# 06_SOM_Console.net
KiCad netlist of a schematic drawn in Altium Designer
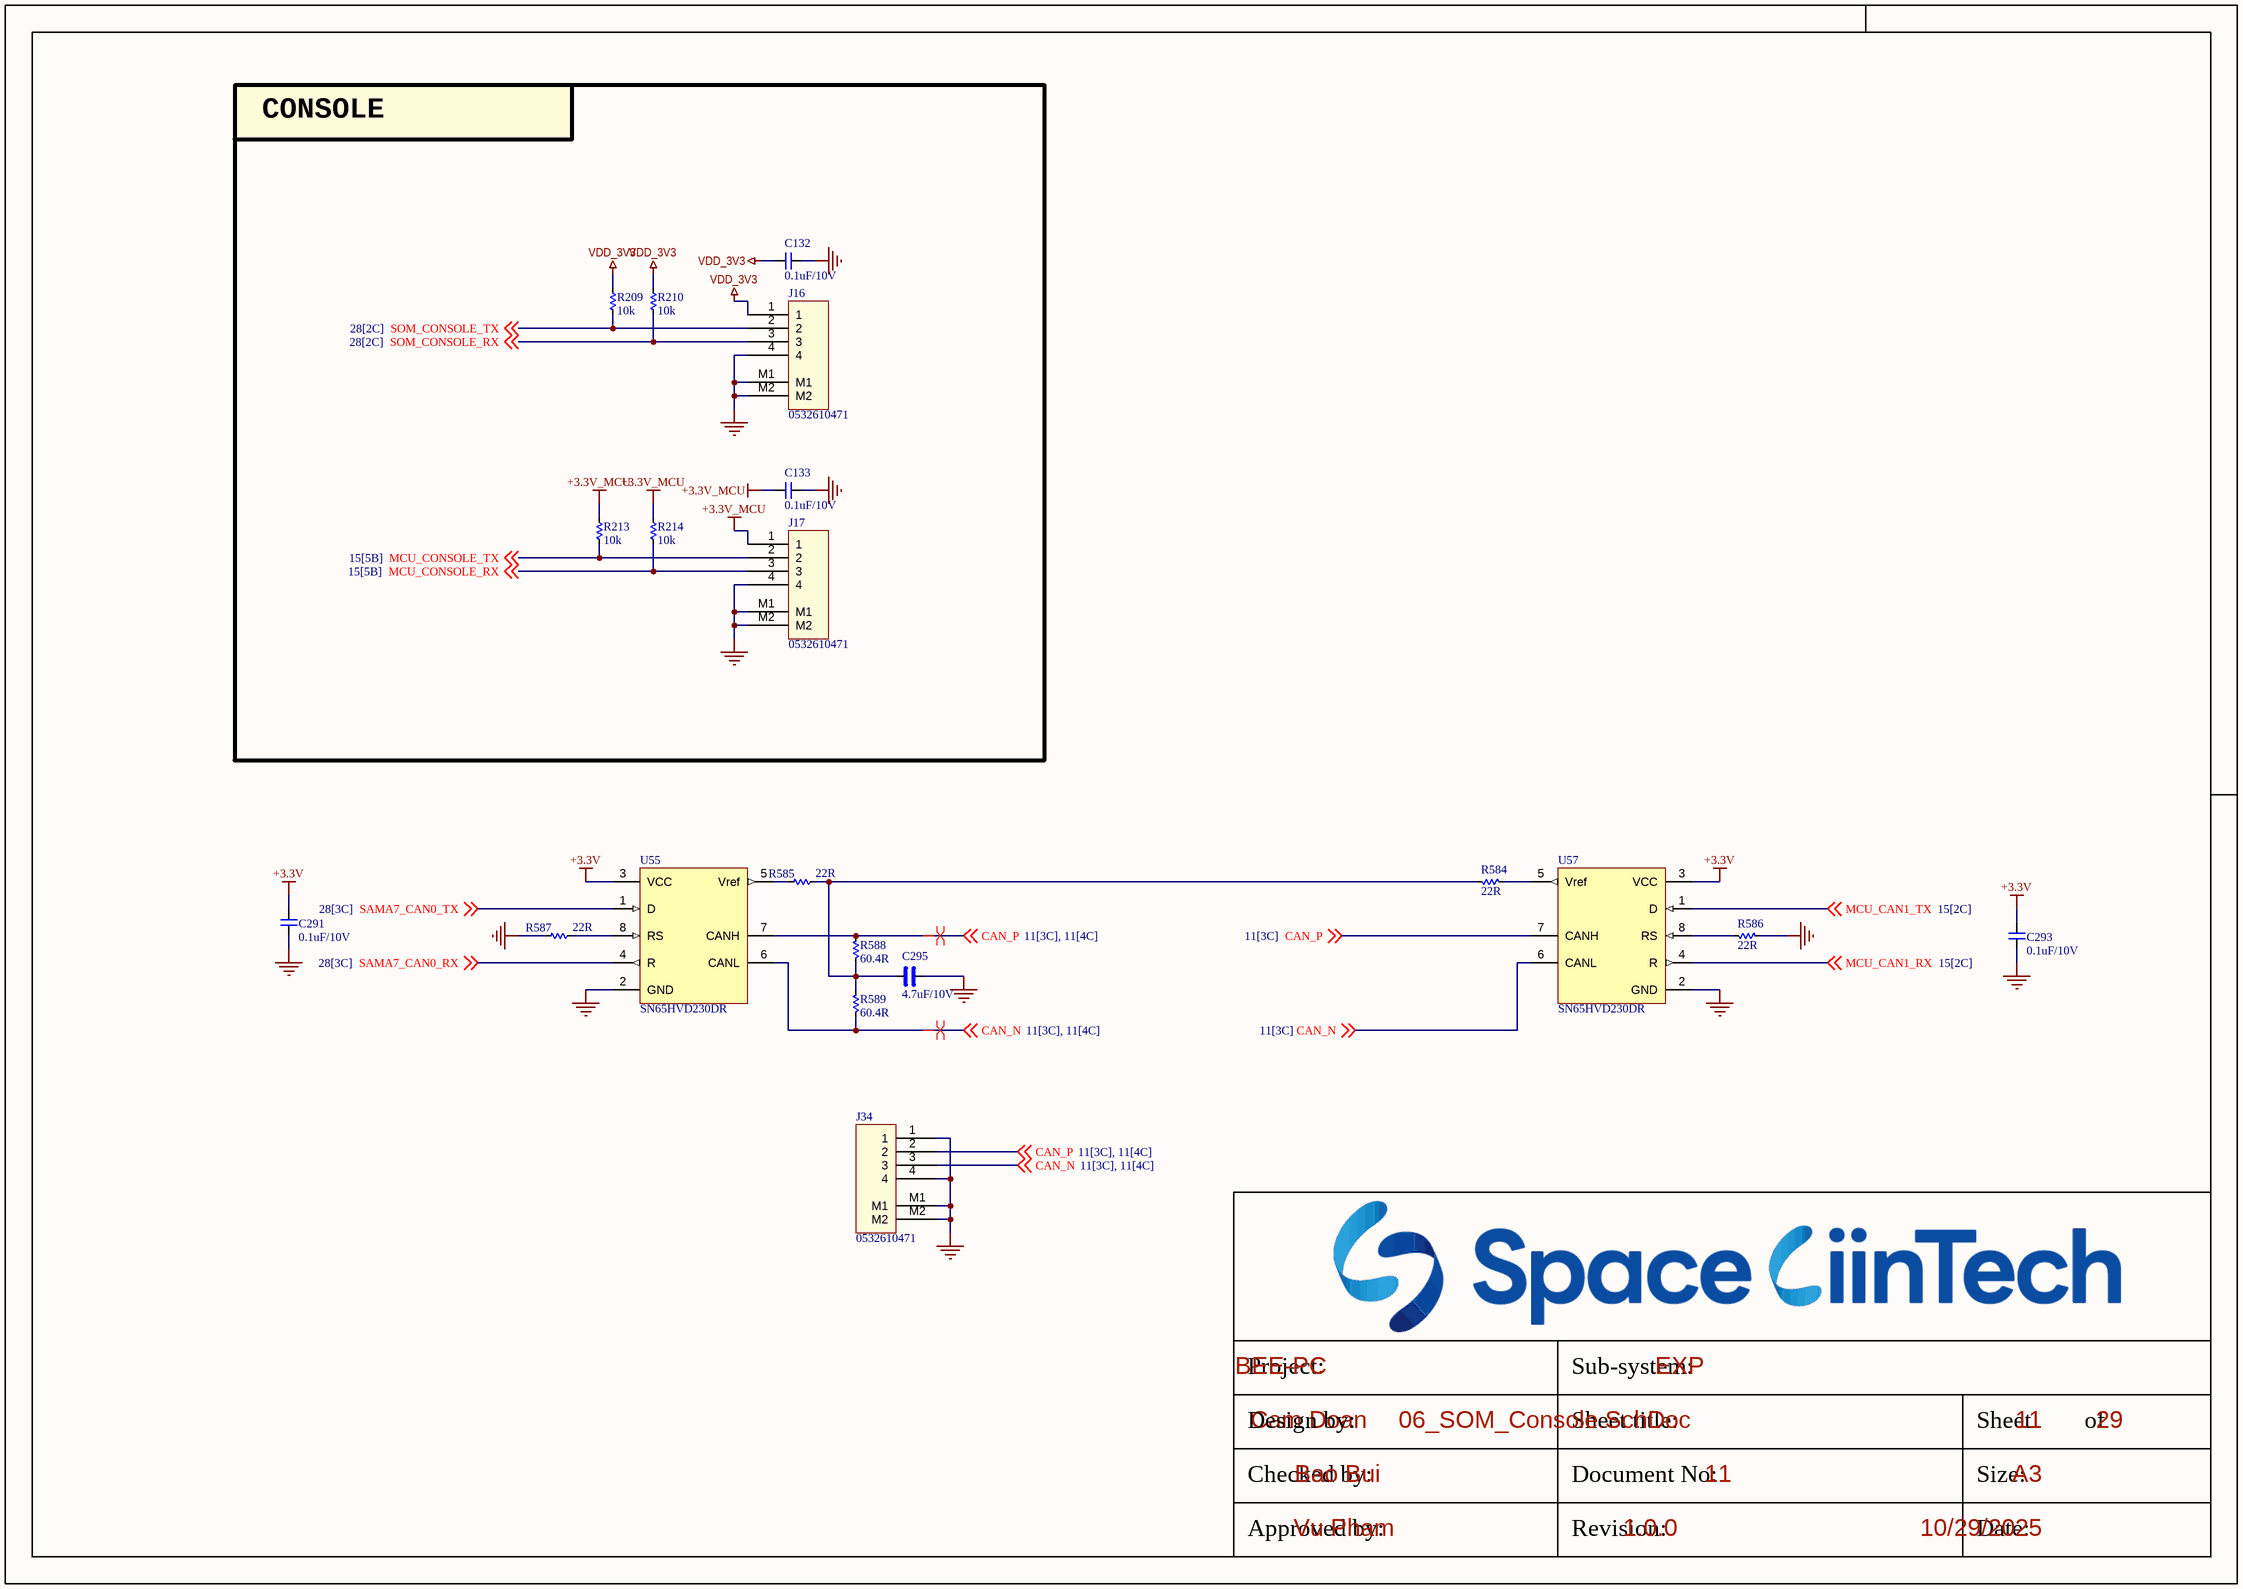
[diagram p0: 06_SOM_Console.SchDoc]

(export (version "E")
  (design (tool "Eeschema 10.0.6"))
  (components
    (comp (ref "C132")
      (value "0.1uF/10V")
      (footprint "CAP_C_1005X60")
      (description "CAP CHIP")
      (libsource (lib "LABLIB") (part "_CAP_C_2"))
    )
    (comp (ref "C133")
      (value "0.1uF/10V")
      (footprint "CAP_C_1005X60")
      (description "CAP CHIP")
      (libsource (lib "LABLIB") (part "_CAP_C_2"))
    )
    (comp (ref "C291")
      (value "0.1uF/10V")
      (footprint "CAP_C_1005X60")
      (description "CAP CHIP")
      (libsource (lib "LABLIB") (part "_CAP_C_2"))
    )
    (comp (ref "C293")
      (value "0.1uF/10V")
      (footprint "CAP_C_1005X60")
      (description "CAP CHIP")
      (libsource (lib "LABLIB") (part "_CAP_C_2"))
    )
    (comp (ref "C295")
      (value "4.7uF/10V")
      (footprint "CAP_C_1005X60")
      (description "CAP CHIP High Value")
      (libsource (lib "LABLIB") (part "_CAP_C_High_2"))
    )
    (comp (ref "J16")
      (value "0532610471")
      (footprint "MOLEX_0532610471")
      (libsource (lib "") (part "Header 4x1_2M_1"))
    )
    (comp (ref "J17")
      (value "0532610471")
      (footprint "MOLEX_0532610471")
      (libsource (lib "") (part "Header 4x1_2M_1"))
    )
    (comp (ref "J34")
      (value "0532610471")
      (footprint "MOLEX_0532610471")
      (libsource (lib "LABLIB") (part "Header 4x1_2M"))
    )
    (comp (ref "R209")
      (value "10k")
      (footprint "RES_C_1005X40")
      (description "RES")
      (libsource (lib "LABLIB") (part "_RES_B_2"))
    )
    (comp (ref "R210")
      (value "10k")
      (footprint "RES_C_1005X40")
      (description "RES")
      (libsource (lib "LABLIB") (part "_RES_B_2"))
    )
    (comp (ref "R213")
      (value "10k")
      (footprint "RES_C_1005X40")
      (description "RES")
      (libsource (lib "LABLIB") (part "_RES_B_2"))
    )
    (comp (ref "R214")
      (value "10k")
      (footprint "RES_C_1005X40")
      (description "RES")
      (libsource (lib "LABLIB") (part "_RES_B_2"))
    )
    (comp (ref "R584")
      (value "22R")
      (footprint "RES_C_1005X40")
      (description "RES")
      (libsource (lib "LABLIB") (part "_RES_B_2"))
    )
    (comp (ref "R585")
      (value "22R")
      (footprint "RES_C_1005X40")
      (description "RES")
      (libsource (lib "LABLIB") (part "_RES_B_2"))
    )
    (comp (ref "R586")
      (value "22R")
      (footprint "RES_C_1005X40")
      (description "RES")
      (libsource (lib "LABLIB") (part "_RES_B_2"))
    )
    (comp (ref "R587")
      (value "22R")
      (footprint "RES_C_1005X40")
      (description "RES")
      (libsource (lib "LABLIB") (part "_RES_B_2"))
    )
    (comp (ref "R588")
      (value "60.4R")
      (footprint "RES_C_1005X40")
      (description "RES")
      (libsource (lib "LABLIB") (part "_RES_B_2"))
    )
    (comp (ref "R589")
      (value "60.4R")
      (footprint "RES_C_1005X40")
      (description "RES")
      (libsource (lib "LABLIB") (part "_RES_B_2"))
    )
    (comp (ref "U55")
      (value "SN65HVD230DR")
      (footprint "SOIC127P602X173-8N")
      (description "IC TRANSCEIVER HALF 1/1 8SOIC")
      (libsource (lib "") (part "IC_CAN_SN65HVD230DR_1"))
    )
    (comp (ref "U57")
      (value "SN65HVD230DR")
      (footprint "SOIC127P602X173-8N")
      (description "IC TRANSCEIVER HALF 1/1 8SOIC")
      (libsource (lib "LABLIB") (part "IC_CAN_SN65HVD230DR"))
    )
  )
  (nets
    (net (code "1") (name "+3.3V") (class "Default")
      (node (ref "C291") (pin "2") (pinfunction "2_2") (pintype "passive"))
      (node (ref "C293") (pin "2") (pinfunction "2_2") (pintype "passive"))
      (node (ref "U55") (pin "3") (pinfunction "VCC_3") (pintype "passive"))
      (node (ref "U57") (pin "3") (pinfunction "VCC_3") (pintype "passive"))
    )
    (net (code "2") (name "+3.3V_MCU") (class "Default")
      (node (ref "C133") (pin "2") (pinfunction "2_2") (pintype "passive"))
      (node (ref "J17") (pin "1") (pinfunction "1_1") (pintype "passive"))
      (node (ref "R213") (pin "2") (pinfunction "2_2") (pintype "passive"))
      (node (ref "R214") (pin "2") (pinfunction "2_2") (pintype "passive"))
    )
    (net (code "3") (name "CAN_N") (class "Default")
      (node (ref "J34") (pin "3") (pinfunction "3_3") (pintype "passive"))
      (node (ref "R589") (pin "1") (pinfunction "1_1") (pintype "passive"))
      (node (ref "U55") (pin "6") (pinfunction "CANL_6") (pintype "passive"))
      (node (ref "U57") (pin "6") (pinfunction "CANL_6") (pintype "passive"))
    )
    (net (code "4") (name "CAN_P") (class "Default")
      (node (ref "J34") (pin "2") (pinfunction "2_2") (pintype "passive"))
      (node (ref "R588") (pin "2") (pinfunction "2_2") (pintype "passive"))
      (node (ref "U55") (pin "7") (pinfunction "CANH_7") (pintype "passive"))
      (node (ref "U57") (pin "7") (pinfunction "CANH_7") (pintype "passive"))
    )
    (net (code "5") (name "GND") (class "Default")
      (node (ref "C132") (pin "1") (pinfunction "1_1") (pintype "passive"))
      (node (ref "C133") (pin "1") (pinfunction "1_1") (pintype "passive"))
      (node (ref "C291") (pin "1") (pinfunction "1_1") (pintype "passive"))
      (node (ref "C293") (pin "1") (pinfunction "1_1") (pintype "passive"))
      (node (ref "C295") (pin "1") (pinfunction "1_1") (pintype "passive"))
      (node (ref "J16") (pin "4") (pinfunction "4_4") (pintype "passive"))
      (node (ref "J16") (pin "M1") (pinfunction "M1_M1") (pintype "passive"))
      (node (ref "J16") (pin "M2") (pinfunction "M2_M2") (pintype "passive"))
      (node (ref "J17") (pin "4") (pinfunction "4_4") (pintype "passive"))
      (node (ref "J17") (pin "M1") (pinfunction "M1_M1") (pintype "passive"))
      (node (ref "J17") (pin "M2") (pinfunction "M2_M2") (pintype "passive"))
      (node (ref "J34") (pin "1") (pinfunction "1_1") (pintype "passive"))
      (node (ref "J34") (pin "4") (pinfunction "4_4") (pintype "passive"))
      (node (ref "J34") (pin "M1") (pinfunction "M1_M1") (pintype "passive"))
      (node (ref "J34") (pin "M2") (pinfunction "M2_M2") (pintype "passive"))
      (node (ref "R586") (pin "2") (pinfunction "2_2") (pintype "passive"))
      (node (ref "R587") (pin "2") (pinfunction "2_2") (pintype "passive"))
      (node (ref "U55") (pin "2") (pinfunction "GND_2") (pintype "passive"))
      (node (ref "U57") (pin "2") (pinfunction "GND_2") (pintype "passive"))
    )
    (net (code "6") (name "MCU_CAN1_RX") (class "Default")
      (node (ref "U57") (pin "4") (pinfunction "R_4") (pintype "output"))
    )
    (net (code "7") (name "MCU_CAN1_TX") (class "Default")
      (node (ref "U57") (pin "1") (pinfunction "D_1") (pintype "input"))
    )
    (net (code "8") (name "MCU_CONSOLE_RX") (class "Default")
      (node (ref "J17") (pin "3") (pinfunction "3_3") (pintype "passive"))
      (node (ref "R214") (pin "1") (pinfunction "1_1") (pintype "passive"))
    )
    (net (code "9") (name "MCU_CONSOLE_TX") (class "Default")
      (node (ref "J17") (pin "2") (pinfunction "2_2") (pintype "passive"))
      (node (ref "R213") (pin "1") (pinfunction "1_1") (pintype "passive"))
    )
    (net (code "10") (name "Net-(C295-Pad2)") (class "Default")
      (node (ref "C295") (pin "2") (pinfunction "2_2") (pintype "passive"))
      (node (ref "R584") (pin "1") (pinfunction "1_1") (pintype "passive"))
      (node (ref "R585") (pin "1") (pinfunction "1_1") (pintype "passive"))
      (node (ref "R588") (pin "1") (pinfunction "1_1") (pintype "passive"))
      (node (ref "R589") (pin "2") (pinfunction "2_2") (pintype "passive"))
    )
    (net (code "11") (name "Net-(U55-RS)") (class "Default")
      (node (ref "R587") (pin "1") (pinfunction "1_1") (pintype "passive"))
      (node (ref "U55") (pin "8") (pinfunction "RS_8") (pintype "input"))
    )
    (net (code "12") (name "Net-(U55-Vref)") (class "Default")
      (node (ref "R585") (pin "2") (pinfunction "2_2") (pintype "passive"))
      (node (ref "U55") (pin "5") (pinfunction "Vref_5") (pintype "output"))
    )
    (net (code "13") (name "Net-(U57-RS)") (class "Default")
      (node (ref "R586") (pin "1") (pinfunction "1_1") (pintype "passive"))
      (node (ref "U57") (pin "8") (pinfunction "RS_8") (pintype "input"))
    )
    (net (code "14") (name "Net-(U57-Vref)") (class "Default")
      (node (ref "R584") (pin "2") (pinfunction "2_2") (pintype "passive"))
      (node (ref "U57") (pin "5") (pinfunction "Vref_5") (pintype "output"))
    )
    (net (code "15") (name "SAMA7_CAN0_RX") (class "Default")
      (node (ref "U55") (pin "4") (pinfunction "R_4") (pintype "output"))
    )
    (net (code "16") (name "SAMA7_CAN0_TX") (class "Default")
      (node (ref "U55") (pin "1") (pinfunction "D_1") (pintype "input"))
    )
    (net (code "17") (name "SOM_CONSOLE_RX") (class "Default")
      (node (ref "J16") (pin "3") (pinfunction "3_3") (pintype "passive"))
      (node (ref "R210") (pin "1") (pinfunction "1_1") (pintype "passive"))
    )
    (net (code "18") (name "SOM_CONSOLE_TX") (class "Default")
      (node (ref "J16") (pin "2") (pinfunction "2_2") (pintype "passive"))
      (node (ref "R209") (pin "1") (pinfunction "1_1") (pintype "passive"))
    )
    (net (code "19") (name "VDD_3V3") (class "Default")
      (node (ref "C132") (pin "2") (pinfunction "2_2") (pintype "passive"))
      (node (ref "J16") (pin "1") (pinfunction "1_1") (pintype "passive"))
      (node (ref "R209") (pin "2") (pinfunction "2_2") (pintype "passive"))
      (node (ref "R210") (pin "2") (pinfunction "2_2") (pintype "passive"))
    )
  )
)
